# easyeda-schematic.net
KiCad netlist of a schematic drawn in EasyEDA
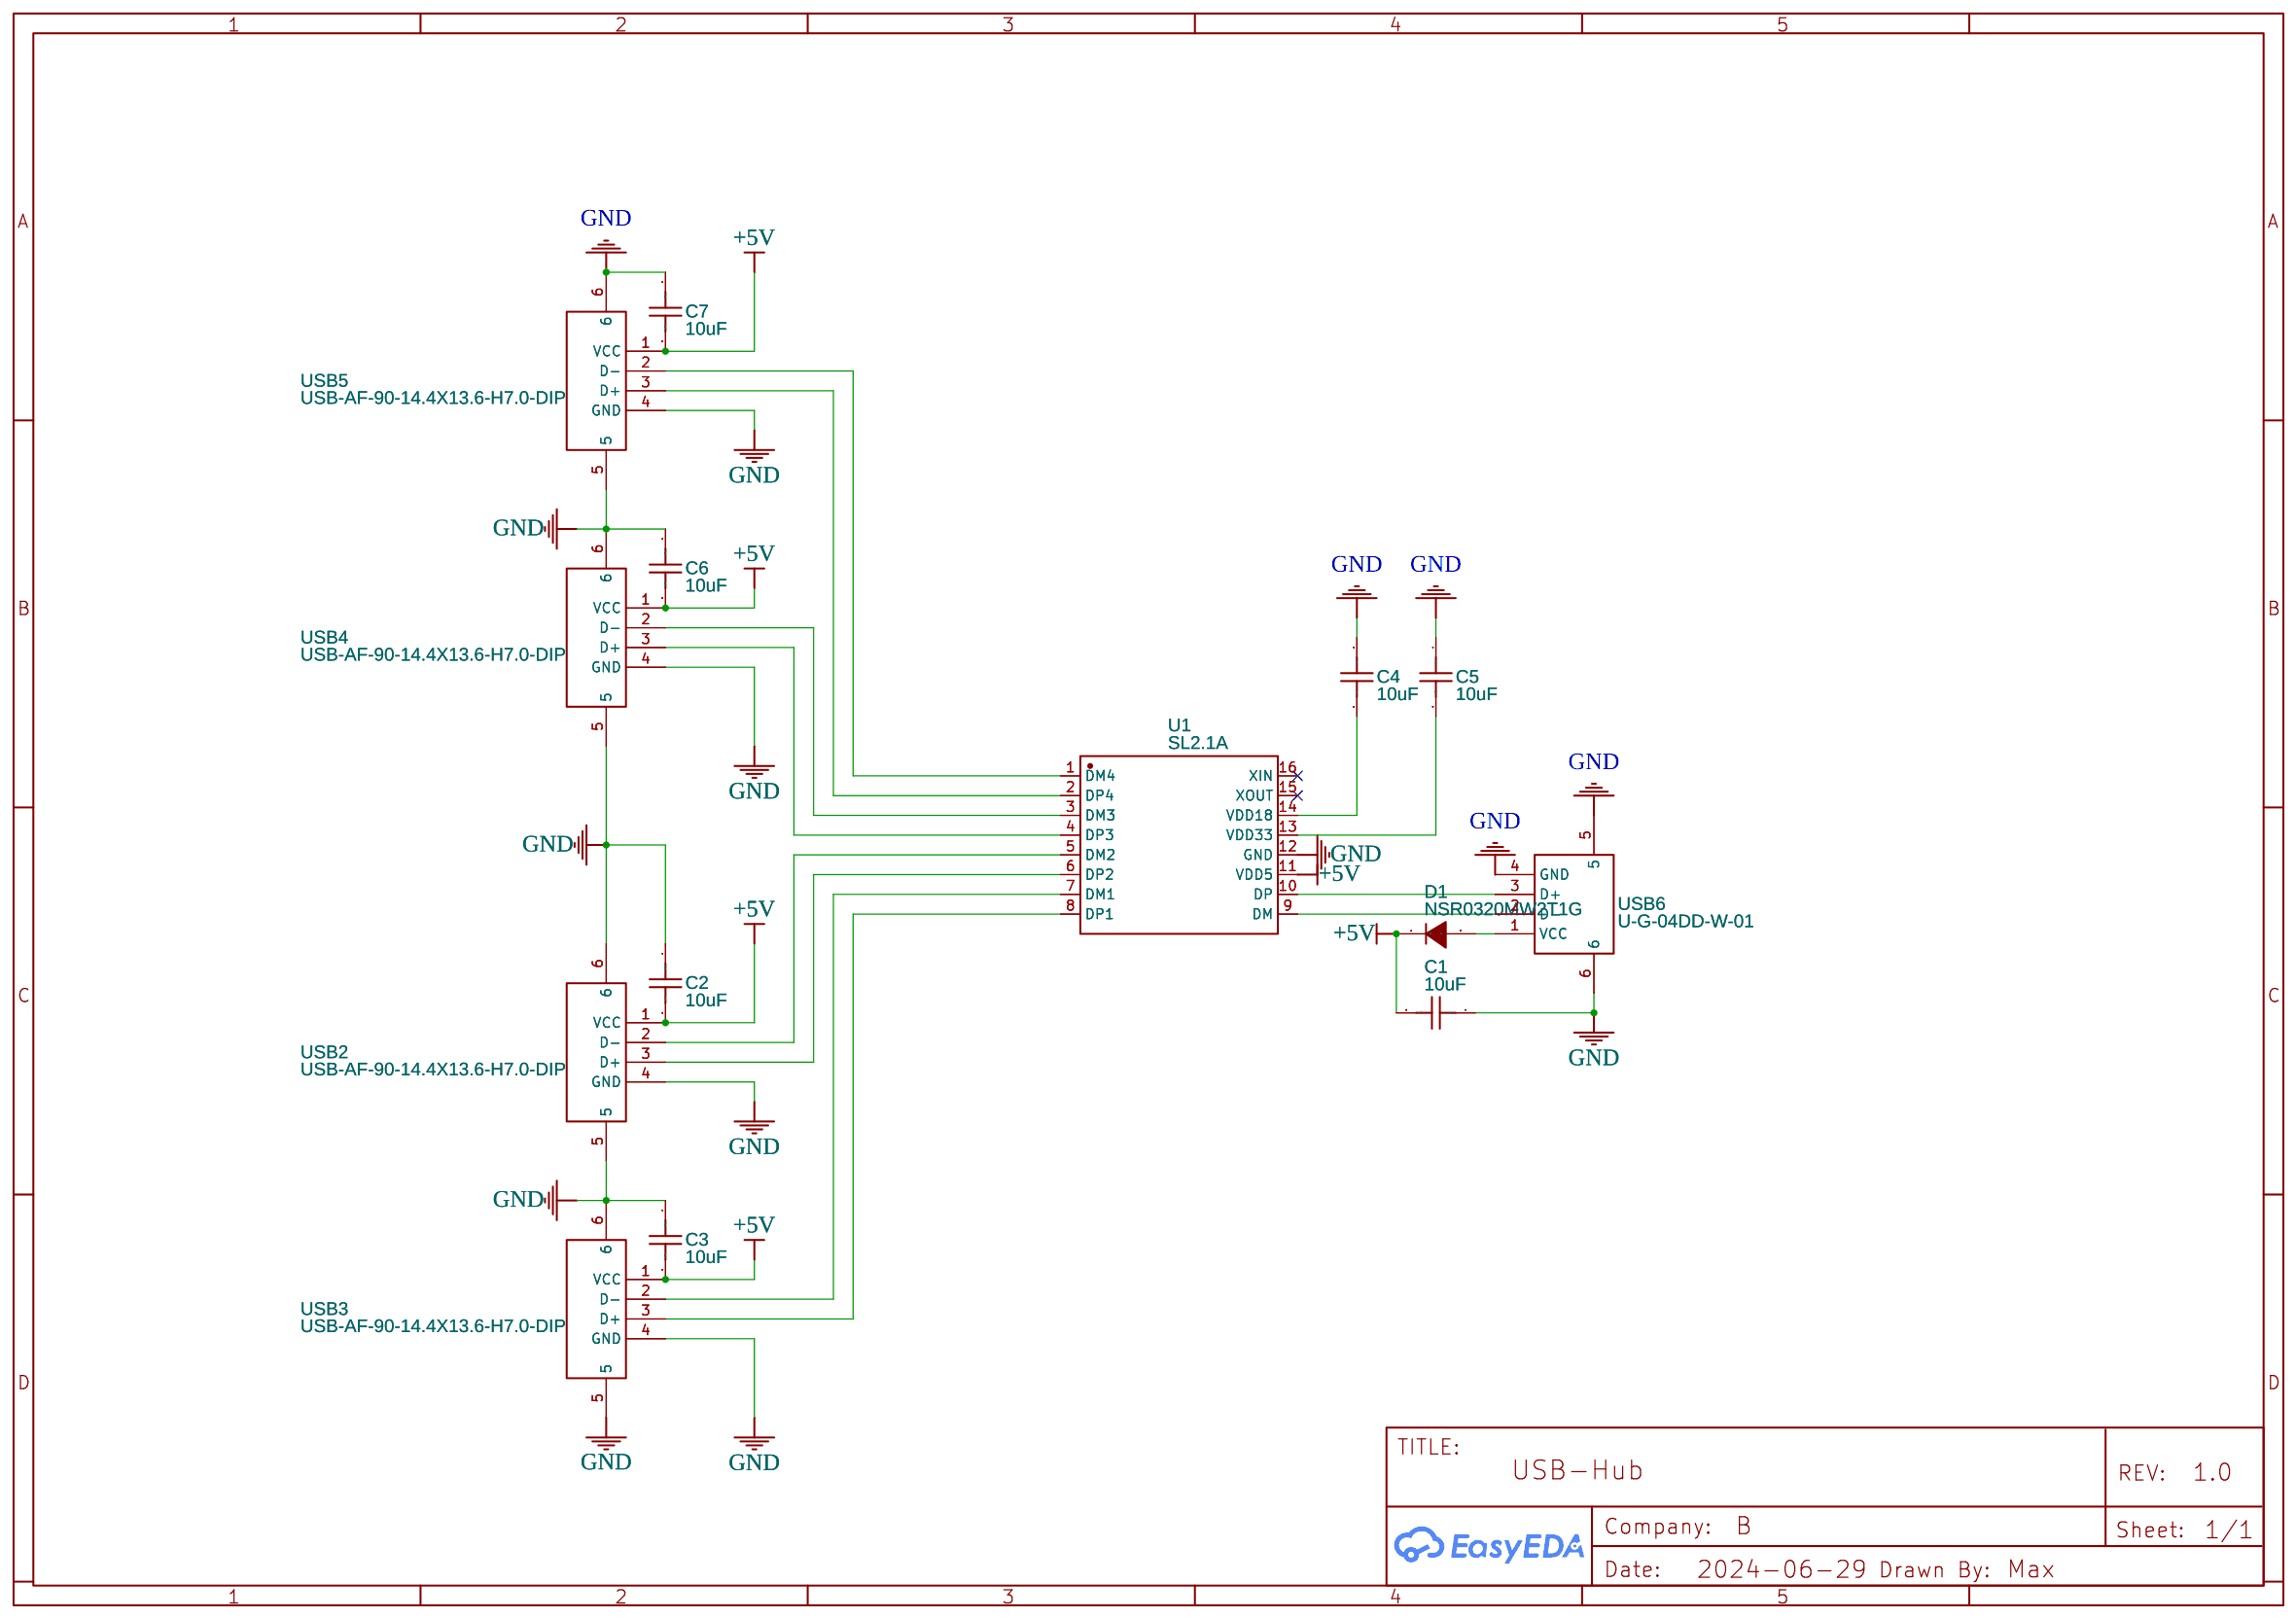
[diagram p0: schematic sheet]

(export (version "E")
  (design (tool "Eeschema 10.0.6"))
  (components
    (comp (ref "C1")
      (value "10uF")
      (fields
        (field (name "Manufacturer Part") "CL10A106KP8NNNC")
        (field (name "Manufacturer") "SAMSUNG(三星)")
      )
      (libsource (lib "") (part "CL10A106KP8NNNC_1"))
    )
    (comp (ref "C2")
      (value "10uF")
      (fields
        (field (name "Manufacturer Part") "CL10A106KP8NNNC")
        (field (name "Manufacturer") "SAMSUNG(三星)")
      )
      (libsource (lib "") (part "CL10A106KP8NNNC"))
    )
    (comp (ref "C3")
      (value "10uF")
      (fields
        (field (name "Manufacturer Part") "CL10A106KP8NNNC")
        (field (name "Manufacturer") "SAMSUNG(三星)")
      )
      (libsource (lib "") (part "CL10A106KP8NNNC"))
    )
    (comp (ref "C4")
      (value "10uF")
      (fields
        (field (name "Manufacturer Part") "CL10A106KP8NNNC")
        (field (name "Manufacturer") "SAMSUNG(三星)")
      )
      (libsource (lib "") (part "CL10A106KP8NNNC"))
    )
    (comp (ref "C5")
      (value "10uF")
      (fields
        (field (name "Manufacturer Part") "CL10A106KP8NNNC")
        (field (name "Manufacturer") "SAMSUNG(三星)")
      )
      (libsource (lib "") (part "CL10A106KP8NNNC"))
    )
    (comp (ref "C6")
      (value "10uF")
      (fields
        (field (name "Manufacturer Part") "CL10A106KP8NNNC")
        (field (name "Manufacturer") "SAMSUNG(三星)")
      )
      (libsource (lib "") (part "CL10A106KP8NNNC"))
    )
    (comp (ref "C7")
      (value "10uF")
      (fields
        (field (name "Manufacturer Part") "CL10A106KP8NNNC")
        (field (name "Manufacturer") "SAMSUNG(三星)")
      )
      (libsource (lib "") (part "CL10A106KP8NNNC"))
    )
    (comp (ref "D1")
      (value "NSR0320MW2T1G")
      (fields (field (name "Manufacturer") "onsemi(安森美)"))
      (libsource (lib "") (part "NSR0320MW2T1G"))
    )
    (comp (ref "U1")
      (value "SL2.1A")
      (fields (field (name "Manufacturer") "CoreChips(和芯润德)"))
      (libsource (lib "") (part "SL2.1A"))
    )
    (comp (ref "USB2")
      (value "USB-AF-90-14.4X13.6-H7.0-DIP")
      (fields (field (name "Manufacturer Part") "903-131A1011D10100") (field (name "Manufacturer") "精拓金"))
      (libsource (lib "") (part "USB-AF-90-14.4X13.6-H7.0-DIP"))
    )
    (comp (ref "USB3")
      (value "USB-AF-90-14.4X13.6-H7.0-DIP")
      (fields (field (name "Manufacturer Part") "903-131A1011D10100") (field (name "Manufacturer") "精拓金"))
      (libsource (lib "") (part "USB-AF-90-14.4X13.6-H7.0-DIP"))
    )
    (comp (ref "USB4")
      (value "USB-AF-90-14.4X13.6-H7.0-DIP")
      (fields (field (name "Manufacturer Part") "903-131A1011D10100") (field (name "Manufacturer") "精拓金"))
      (libsource (lib "") (part "USB-AF-90-14.4X13.6-H7.0-DIP"))
    )
    (comp (ref "USB5")
      (value "USB-AF-90-14.4X13.6-H7.0-DIP")
      (fields (field (name "Manufacturer Part") "903-131A1011D10100") (field (name "Manufacturer") "精拓金"))
      (libsource (lib "") (part "USB-AF-90-14.4X13.6-H7.0-DIP"))
    )
    (comp (ref "USB6")
      (value "U-G-04DD-W-01")
      (fields (field (name "Manufacturer Part") "U-G-O4DD-W-1") (field (name "Manufacturer") "韩国韩荣"))
      (libsource (lib "") (part "U-G-04DD-W-01"))
    )
  )
  (nets
    (net (code "1") (name "+5V") (class "Default")
      (node (ref "C1") (pin "2") (pinfunction "2_2") (pintype "unspecified"))
      (node (ref "C2") (pin "2") (pinfunction "2_2") (pintype "unspecified"))
      (node (ref "C3") (pin "2") (pinfunction "2_2") (pintype "unspecified"))
      (node (ref "C6") (pin "2") (pinfunction "2_2") (pintype "unspecified"))
      (node (ref "C7") (pin "2") (pinfunction "2_2") (pintype "unspecified"))
      (node (ref "D1") (pin "1") (pinfunction "C_1") (pintype "unspecified"))
      (node (ref "U1") (pin "11") (pinfunction "VDD5_11") (pintype "unspecified"))
      (node (ref "USB2") (pin "1") (pinfunction "VCC_1") (pintype "unspecified"))
      (node (ref "USB3") (pin "1") (pinfunction "VCC_1") (pintype "unspecified"))
      (node (ref "USB4") (pin "1") (pinfunction "VCC_1") (pintype "unspecified"))
      (node (ref "USB5") (pin "1") (pinfunction "VCC_1") (pintype "unspecified"))
    )
    (net (code "2") (name "GND") (class "Default")
      (node (ref "C1") (pin "1") (pinfunction "1_1") (pintype "unspecified"))
      (node (ref "C2") (pin "1") (pinfunction "1_1") (pintype "unspecified"))
      (node (ref "C3") (pin "1") (pinfunction "1_1") (pintype "unspecified"))
      (node (ref "C4") (pin "1") (pinfunction "1_1") (pintype "unspecified"))
      (node (ref "C5") (pin "1") (pinfunction "1_1") (pintype "unspecified"))
      (node (ref "C6") (pin "1") (pinfunction "1_1") (pintype "unspecified"))
      (node (ref "C7") (pin "1") (pinfunction "1_1") (pintype "unspecified"))
      (node (ref "U1") (pin "12") (pinfunction "GND_12") (pintype "unspecified"))
      (node (ref "USB2") (pin "4") (pinfunction "GND_4") (pintype "unspecified"))
      (node (ref "USB2") (pin "5") (pinfunction "5_5") (pintype "unspecified"))
      (node (ref "USB2") (pin "6") (pinfunction "6_6") (pintype "unspecified"))
      (node (ref "USB3") (pin "4") (pinfunction "GND_4") (pintype "unspecified"))
      (node (ref "USB3") (pin "5") (pinfunction "5_5") (pintype "unspecified"))
      (node (ref "USB3") (pin "6") (pinfunction "6_6") (pintype "unspecified"))
      (node (ref "USB4") (pin "4") (pinfunction "GND_4") (pintype "unspecified"))
      (node (ref "USB4") (pin "5") (pinfunction "5_5") (pintype "unspecified"))
      (node (ref "USB4") (pin "6") (pinfunction "6_6") (pintype "unspecified"))
      (node (ref "USB5") (pin "4") (pinfunction "GND_4") (pintype "unspecified"))
      (node (ref "USB5") (pin "5") (pinfunction "5_5") (pintype "unspecified"))
      (node (ref "USB5") (pin "6") (pinfunction "6_6") (pintype "unspecified"))
      (node (ref "USB6") (pin "4") (pinfunction "GND_4") (pintype "unspecified"))
      (node (ref "USB6") (pin "5") (pinfunction "5_5") (pintype "unspecified"))
      (node (ref "USB6") (pin "6") (pinfunction "6_6") (pintype "unspecified"))
    )
    (net (code "3") (name "Net-(D1-A)") (class "Default")
      (node (ref "D1") (pin "2") (pinfunction "A_2") (pintype "unspecified"))
      (node (ref "USB6") (pin "1") (pinfunction "VCC_1") (pintype "unspecified"))
    )
    (net (code "4") (name "Net-(U1-DM)") (class "Default")
      (node (ref "U1") (pin "9") (pinfunction "DM_9") (pintype "unspecified"))
      (node (ref "USB6") (pin "2") (pinfunction "D-_2") (pintype "unspecified"))
    )
    (net (code "5") (name "Net-(U1-DM1)") (class "Default")
      (node (ref "U1") (pin "7") (pinfunction "DM1_7") (pintype "unspecified"))
      (node (ref "USB3") (pin "2") (pinfunction "D-_2") (pintype "unspecified"))
    )
    (net (code "6") (name "Net-(U1-DM2)") (class "Default")
      (node (ref "U1") (pin "5") (pinfunction "DM2_5") (pintype "unspecified"))
      (node (ref "USB2") (pin "2") (pinfunction "D-_2") (pintype "unspecified"))
    )
    (net (code "7") (name "Net-(U1-DM3)") (class "Default")
      (node (ref "U1") (pin "3") (pinfunction "DM3_3") (pintype "unspecified"))
      (node (ref "USB4") (pin "2") (pinfunction "D-_2") (pintype "unspecified"))
    )
    (net (code "8") (name "Net-(U1-DM4)") (class "Default")
      (node (ref "U1") (pin "1") (pinfunction "DM4_1") (pintype "unspecified"))
      (node (ref "USB5") (pin "2") (pinfunction "D-_2") (pintype "unspecified"))
    )
    (net (code "9") (name "Net-(U1-DP)") (class "Default")
      (node (ref "U1") (pin "10") (pinfunction "DP_10") (pintype "unspecified"))
      (node (ref "USB6") (pin "3") (pinfunction "D+_3") (pintype "unspecified"))
    )
    (net (code "10") (name "Net-(U1-DP1)") (class "Default")
      (node (ref "U1") (pin "8") (pinfunction "DP1_8") (pintype "unspecified"))
      (node (ref "USB3") (pin "3") (pinfunction "D+_3") (pintype "unspecified"))
    )
    (net (code "11") (name "Net-(U1-DP2)") (class "Default")
      (node (ref "U1") (pin "6") (pinfunction "DP2_6") (pintype "unspecified"))
      (node (ref "USB2") (pin "3") (pinfunction "D+_3") (pintype "unspecified"))
    )
    (net (code "12") (name "Net-(U1-DP3)") (class "Default")
      (node (ref "U1") (pin "4") (pinfunction "DP3_4") (pintype "unspecified"))
      (node (ref "USB4") (pin "3") (pinfunction "D+_3") (pintype "unspecified"))
    )
    (net (code "13") (name "Net-(U1-DP4)") (class "Default")
      (node (ref "U1") (pin "2") (pinfunction "DP4_2") (pintype "unspecified"))
      (node (ref "USB5") (pin "3") (pinfunction "D+_3") (pintype "unspecified"))
    )
    (net (code "14") (name "Net-(U1-VDD18)") (class "Default")
      (node (ref "C4") (pin "2") (pinfunction "2_2") (pintype "unspecified"))
      (node (ref "U1") (pin "14") (pinfunction "VDD18_14") (pintype "unspecified"))
    )
    (net (code "15") (name "Net-(U1-VDD33)") (class "Default")
      (node (ref "C5") (pin "2") (pinfunction "2_2") (pintype "unspecified"))
      (node (ref "U1") (pin "13") (pinfunction "VDD33_13") (pintype "unspecified"))
    )
    (net (code "16") (name "unconnected-(U1-XIN-Pad16)") (class "Default")
      (node (ref "U1") (pin "16") (pinfunction "XIN_16") (pintype "unspecified+no_connect"))
    )
    (net (code "17") (name "unconnected-(U1-XOUT-Pad15)") (class "Default")
      (node (ref "U1") (pin "15") (pinfunction "XOUT_15") (pintype "unspecified+no_connect"))
    )
  )
)
